# design.net
KiCad netlist of a schematic drawn in Altium Designer
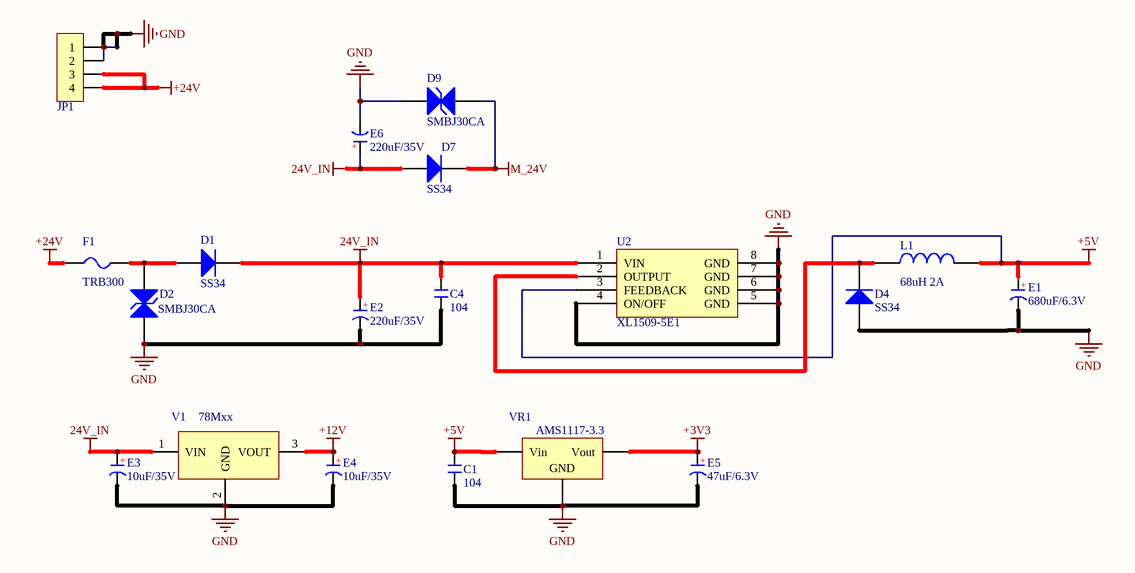
[diagram p0: 电源.SchDoc]

(export (version "E")
  (design (tool "Eeschema 10.0.6"))
  (components
    (comp (ref "C1")
      (value "104")
      (footprint "C 0603")
      (description "无极性贴片电容")
      (fields (field (name "版权归属") "源创客"))
      (libsource (lib "源创客") (part "C"))
    )
    (comp (ref "C4")
      (value "104")
      (footprint "C 0603")
      (description "无极性贴片电容")
      (fields (field (name "版权归属") "源创客"))
      (libsource (lib "源创客") (part "C"))
    )
    (comp (ref "D1")
      (value "SS34")
      (footprint "SMA(DO-214AC)_S1")
      (description "二极管")
      (libsource (lib "Miscellaneous Devices LC") (part "SMA(DO-214AC) SS54"))
    )
    (comp (ref "D2")
      (value "SMBJ30CA")
      (footprint "LC-SMA(DO-214AC)_S1")
      (description "TVS")
      (libsource (lib "Miscellaneous Devices LC") (part "SMB/DO-214AA P6SMB6.8CA"))
    )
    (comp (ref "D4")
      (value "SS34")
      (footprint "SMA(DO-214AC)_S1")
      (description "二极管")
      (libsource (lib "Miscellaneous Devices LC") (part "SMA(DO-214AC) SS54"))
    )
    (comp (ref "D7")
      (value "SS34")
      (footprint "SMA(DO-214AC)_S1")
      (description "二极管")
      (libsource (lib "Miscellaneous Devices LC") (part "SMA(DO-214AC) SS54"))
    )
    (comp (ref "D9")
      (value "SMBJ30CA")
      (footprint "LC-SMA(DO-214AC)_S1")
      (description "TVS")
      (libsource (lib "Miscellaneous Devices LC") (part "SMB/DO-214AA P6SMB6.8CA"))
    )
    (comp (ref "E1")
      (value "680uF/6.3V")
      (footprint "CM E(8*10.2)")
      (description "贴片电解电容")
      (fields (field (name "版权归属") "源创客"))
      (libsource (lib "源创客") (part "C-CM"))
    )
    (comp (ref "E2")
      (value "220uF/35V")
      (footprint "CM E(8*10.2)")
      (description "贴片电解电容")
      (fields (field (name "版权归属") "源创客"))
      (libsource (lib "源创客") (part "C-CM"))
    )
    (comp (ref "E3")
      (value "10uF/35V")
      (footprint "CM B(4*5.4)")
      (description "贴片电解电容")
      (fields (field (name "版权归属") "源创客"))
      (libsource (lib "源创客") (part "C-CM"))
    )
    (comp (ref "E4")
      (value "10uF/35V")
      (footprint "CM B(4*5.4)")
      (description "贴片电解电容")
      (fields (field (name "版权归属") "源创客"))
      (libsource (lib "源创客") (part "C-CM"))
    )
    (comp (ref "E5")
      (value "47uF/6.3V")
      (footprint "CM C(5*5.4)")
      (description "贴片电解电容")
      (fields (field (name "版权归属") "源创客"))
      (libsource (lib "源创客") (part "C-CM"))
    )
    (comp (ref "E6")
      (value "220uF/35V")
      (footprint "CM E(8*10.2)")
      (description "贴片电解电容")
      (fields (field (name "版权归属") "源创客"))
      (libsource (lib "源创客") (part "C-CM"))
    )
    (comp (ref "F1")
      (value "TRB300")
      (footprint "5.08mm")
      (description "直插保险丝")
      (fields (field (name "版权归属") "源创客"))
      (libsource (lib "源创客") (part "FU"))
    )
    (comp (ref "JP1")
      (value "XH-2.54-4P")
      (footprint "XH2.54-4P")
      (description "4P接插件")
      (fields (field (name "版权归属") "源创客"))
      (libsource (lib "源创客") (part "Header 4"))
    )
    (comp (ref "L1")
      (value "68uH 2A")
      (footprint "CDRH74")
      (description "INDUCTOR")
      (libsource (lib "电感") (part "INDUCTOR"))
    )
    (comp (ref "U2")
      (value "XL1509-5E1")
      (footprint "SOP-8_150mil")
      (description "DC-DC芯片")
      (libsource (lib "this") (part "XL1509-3.3E1"))
    )
    (comp (ref "V1")
      (value "78Mxx")
      (footprint "LC-TO-252-2")
      (description "线性稳压芯片")
      (fields (field (name "版权归属") "源创客"))
      (libsource (lib "源创客") (part "78Mxx"))
    )
    (comp (ref "VR1")
      (value "AMS1117-3.3")
      (footprint "SOT-223")
      (description "低压差线性稳压(LDO)")
      (libsource (lib "Miscellaneous Devices LC") (part "SOT-223 AMS1117-3.3"))
    )
  )
  (nets
    (net (code "1") (name "+3V3") (class "Default")
      (node (ref "E5") (pin "1") (pinfunction "A_1") (pintype "passive"))
      (node (ref "VR1") (pin "2") (pinfunction "Vout_2") (pintype "passive"))
    )
    (net (code "2") (name "+5V") (class "Default")
      (node (ref "C1") (pin "2") (pinfunction "2_2") (pintype "passive"))
      (node (ref "E1") (pin "1") (pinfunction "A_1") (pintype "passive"))
      (node (ref "L1") (pin "2") (pinfunction "2_2") (pintype "passive"))
      (node (ref "U2") (pin "3") (pinfunction "FEEDBACK_3") (pintype "passive"))
      (node (ref "VR1") (pin "3") (pinfunction "Vin_3") (pintype "passive"))
    )
    (net (code "3") (name "+12V") (class "Default")
      (node (ref "E4") (pin "1") (pinfunction "A_1") (pintype "passive"))
      (node (ref "V1") (pin "3") (pinfunction "VOUT_3") (pintype "passive"))
    )
    (net (code "4") (name "+24V") (class "Default")
      (node (ref "F1") (pin "1") (pinfunction "1_1") (pintype "passive"))
      (node (ref "JP1") (pin "3") (pinfunction "3_3") (pintype "passive"))
      (node (ref "JP1") (pin "4") (pinfunction "4_4") (pintype "passive"))
    )
    (net (code "5") (name "24V_IN") (class "Default")
      (node (ref "C4") (pin "2") (pinfunction "2_2") (pintype "passive"))
      (node (ref "D1") (pin "2") (pinfunction "K_2") (pintype "passive"))
      (node (ref "D7") (pin "1") (pinfunction "A_1") (pintype "passive"))
      (node (ref "E2") (pin "1") (pinfunction "A_1") (pintype "passive"))
      (node (ref "E3") (pin "1") (pinfunction "A_1") (pintype "passive"))
      (node (ref "E6") (pin "1") (pinfunction "A_1") (pintype "passive"))
      (node (ref "U2") (pin "1") (pinfunction "VIN_1") (pintype "passive"))
      (node (ref "V1") (pin "1") (pinfunction "VIN_1") (pintype "passive"))
    )
    (net (code "6") (name "GND") (class "Default")
      (node (ref "C1") (pin "1") (pinfunction "1_1") (pintype "passive"))
      (node (ref "C4") (pin "1") (pinfunction "1_1") (pintype "passive"))
      (node (ref "D2") (pin "1") (pinfunction "A_1") (pintype "passive"))
      (node (ref "D4") (pin "1") (pinfunction "A_1") (pintype "passive"))
      (node (ref "D9") (pin "1") (pinfunction "A_1") (pintype "passive"))
      (node (ref "E1") (pin "2") (pinfunction "K_2") (pintype "passive"))
      (node (ref "E2") (pin "2") (pinfunction "K_2") (pintype "passive"))
      (node (ref "E3") (pin "2") (pinfunction "K_2") (pintype "passive"))
      (node (ref "E4") (pin "2") (pinfunction "K_2") (pintype "passive"))
      (node (ref "E5") (pin "2") (pinfunction "K_2") (pintype "passive"))
      (node (ref "E6") (pin "2") (pinfunction "K_2") (pintype "passive"))
      (node (ref "JP1") (pin "1") (pinfunction "1_1") (pintype "passive"))
      (node (ref "JP1") (pin "2") (pinfunction "2_2") (pintype "passive"))
      (node (ref "U2") (pin "4") (pinfunction "ON/OFF_4") (pintype "passive"))
      (node (ref "U2") (pin "5") (pinfunction "GND_5") (pintype "passive"))
      (node (ref "U2") (pin "6") (pinfunction "GND_6") (pintype "passive"))
      (node (ref "U2") (pin "7") (pinfunction "GND_7") (pintype "passive"))
      (node (ref "U2") (pin "8") (pinfunction "GND_8") (pintype "passive"))
      (node (ref "V1") (pin "2") (pinfunction "GND_2") (pintype "passive"))
      (node (ref "VR1") (pin "1") (pinfunction "GND_1") (pintype "passive"))
    )
    (net (code "7") (name "M_24V") (class "Default")
      (node (ref "D7") (pin "2") (pinfunction "K_2") (pintype "passive"))
      (node (ref "D9") (pin "2") (pinfunction "K_2") (pintype "passive"))
    )
    (net (code "8") (name "Net-(D1-A)") (class "Default")
      (node (ref "D1") (pin "1") (pinfunction "A_1") (pintype "passive"))
      (node (ref "D2") (pin "2") (pinfunction "K_2") (pintype "passive"))
      (node (ref "F1") (pin "2") (pinfunction "2_2") (pintype "passive"))
    )
    (net (code "9") (name "Net-(D4-K)") (class "Default")
      (node (ref "D4") (pin "2") (pinfunction "K_2") (pintype "passive"))
      (node (ref "L1") (pin "1") (pinfunction "1_1") (pintype "passive"))
      (node (ref "U2") (pin "2") (pinfunction "OUTPUT_2") (pintype "passive"))
    )
  )
)
